# Schematic.net
KiCad netlist of a schematic drawn in Altium Designer
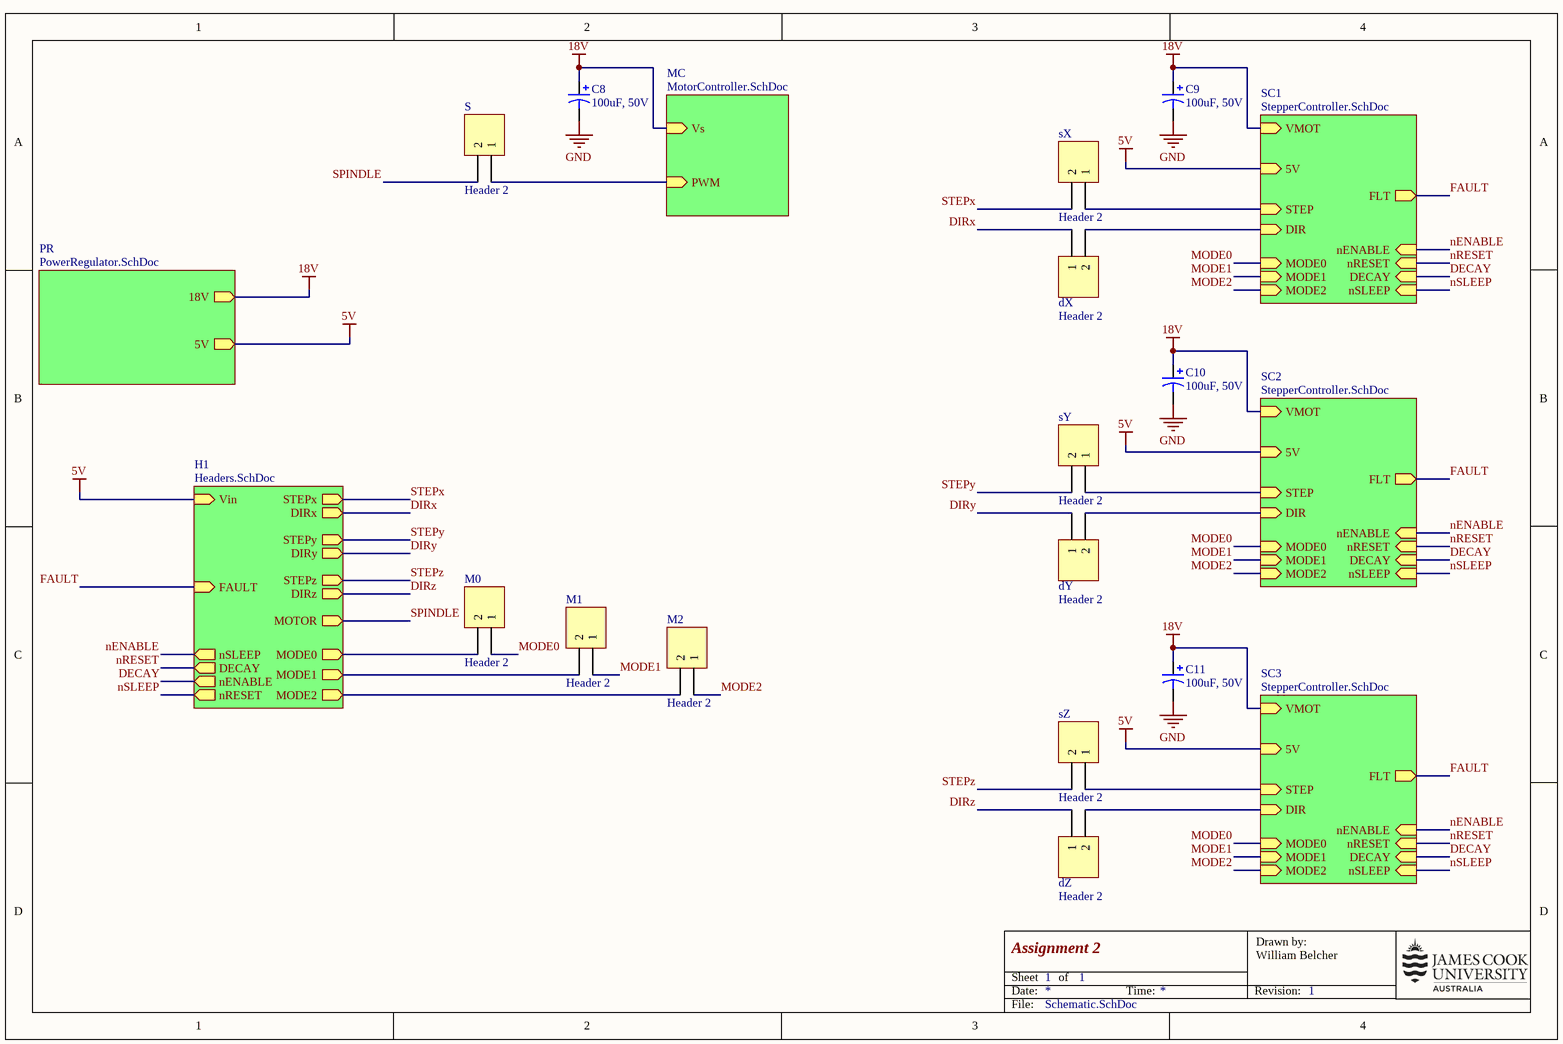
[diagram p0: Schematic.SchDoc]

(export (version "E")
  (design (tool "Eeschema 10.0.6"))
  (components
    (comp (ref "C8")
      (value "100uF, 50V")
      (footprint "Capacitor radial 8mm")
      (description "Electrolytic Capacitor, 100 µF, 50 V, ± 20%, Radial Leaded, 8 mm")
      (libsource (lib "JCULibrary_AS2") (part "Cap 100uF, 50V, THT radial"))
    )
    (comp (ref "C9")
      (value "100uF, 50V")
      (footprint "Capacitor radial 8mm")
      (description "Electrolytic Capacitor, 100 µF, 50 V, ± 20%, Radial Leaded, 8 mm")
      (libsource (lib "JCULibrary_AS2") (part "Cap 100uF, 50V, THT radial"))
    )
    (comp (ref "C10")
      (value "100uF, 50V")
      (footprint "Capacitor radial 8mm")
      (description "Electrolytic Capacitor, 100 µF, 50 V, ± 20%, Radial Leaded, 8 mm")
      (libsource (lib "JCULibrary_AS2") (part "Cap 100uF, 50V, THT radial"))
    )
    (comp (ref "C11")
      (value "100uF, 50V")
      (footprint "Capacitor radial 8mm")
      (description "Electrolytic Capacitor, 100 µF, 50 V, ± 20%, Radial Leaded, 8 mm")
      (libsource (lib "JCULibrary_AS2") (part "Cap 100uF, 50V, THT radial"))
    )
    (comp (ref "dX")
      (value "Header 2")
      (footprint "HDR1X2")
      (description "Header, 2-Pin")
      (fields (field (name "PUBLISHER") "Altium Limited"))
      (libsource (lib "") (part "Header 2_1"))
    )
    (comp (ref "dY")
      (value "Header 2")
      (footprint "HDR1X2")
      (description "Header, 2-Pin")
      (fields (field (name "PUBLISHER") "Altium Limited"))
      (libsource (lib "") (part "Header 2_1"))
    )
    (comp (ref "dZ")
      (value "Header 2")
      (footprint "HDR1X2")
      (description "Header, 2-Pin")
      (fields (field (name "PUBLISHER") "Altium Limited"))
      (libsource (lib "") (part "Header 2_1"))
    )
    (comp (ref "M0")
      (value "Header 2")
      (footprint "HDR1X2")
      (description "Header, 2-Pin")
      (fields (field (name "PUBLISHER") "Altium Limited"))
      (libsource (lib "Miscellaneous Connectors") (part "Header 2"))
    )
    (comp (ref "M1")
      (value "Header 2")
      (footprint "HDR1X2")
      (description "Header, 2-Pin")
      (fields (field (name "PUBLISHER") "Altium Limited"))
      (libsource (lib "Miscellaneous Connectors") (part "Header 2"))
    )
    (comp (ref "M2")
      (value "Header 2")
      (footprint "HDR1X2")
      (description "Header, 2-Pin")
      (fields (field (name "PUBLISHER") "Altium Limited"))
      (libsource (lib "Miscellaneous Connectors") (part "Header 2"))
    )
    (comp (ref "S")
      (value "Header 2")
      (footprint "HDR1X2")
      (description "Header, 2-Pin")
      (fields (field (name "PUBLISHER") "Altium Limited"))
      (libsource (lib "Miscellaneous Connectors") (part "Header 2"))
    )
    (comp (ref "sX")
      (value "Header 2")
      (footprint "HDR1X2")
      (description "Header, 2-Pin")
      (fields (field (name "PUBLISHER") "Altium Limited"))
      (libsource (lib "Miscellaneous Connectors") (part "Header 2"))
    )
    (comp (ref "sY")
      (value "Header 2")
      (footprint "HDR1X2")
      (description "Header, 2-Pin")
      (fields (field (name "PUBLISHER") "Altium Limited"))
      (libsource (lib "Miscellaneous Connectors") (part "Header 2"))
    )
    (comp (ref "sZ")
      (value "Header 2")
      (footprint "HDR1X2")
      (description "Header, 2-Pin")
      (fields (field (name "PUBLISHER") "Altium Limited"))
      (libsource (lib "Miscellaneous Connectors") (part "Header 2"))
    )
  )
  (nets
    (net (code "2") (name "/DIR") (class "Default")
      (node (ref "dY") (pin "2") (pinfunction "2_2") (pintype "passive"))
    )
    (net (code "3") (name "/DIR_1") (class "Default")
      (node (ref "dZ") (pin "2") (pinfunction "2_2") (pintype "passive"))
    )
    (net (code "4") (name "/DIR_2") (class "Default")
      (node (ref "dX") (pin "2") (pinfunction "2_2") (pintype "passive"))
    )
    (net (code "5") (name "/DIRx") (class "Default")
      (node (ref "dX") (pin "1") (pinfunction "1_1") (pintype "passive"))
    )
    (net (code "6") (name "/DIRy") (class "Default")
      (node (ref "dY") (pin "1") (pinfunction "1_1") (pintype "passive"))
    )
    (net (code "7") (name "/DIRz") (class "Default")
      (node (ref "dZ") (pin "1") (pinfunction "1_1") (pintype "passive"))
    )
    (net (code "9") (name "/MODE0") (class "Default")
      (node (ref "M0") (pin "1") (pinfunction "1_1") (pintype "passive"))
    )
    (net (code "10") (name "/MODE0_1") (class "Default")
      (node (ref "M0") (pin "2") (pinfunction "2_2") (pintype "passive"))
    )
    (net (code "11") (name "/MODE1") (class "Default")
      (node (ref "M1") (pin "1") (pinfunction "1_1") (pintype "passive"))
    )
    (net (code "12") (name "/MODE1_1") (class "Default")
      (node (ref "M1") (pin "2") (pinfunction "2_2") (pintype "passive"))
    )
    (net (code "13") (name "/MODE2") (class "Default")
      (node (ref "M2") (pin "1") (pinfunction "1_1") (pintype "passive"))
    )
    (net (code "14") (name "/MODE2_1") (class "Default")
      (node (ref "M2") (pin "2") (pinfunction "2_2") (pintype "passive"))
    )
    (net (code "15") (name "/PWM") (class "Default")
      (node (ref "S") (pin "1") (pinfunction "1_1") (pintype "passive"))
    )
    (net (code "16") (name "/SPINDLE") (class "Default")
      (node (ref "S") (pin "2") (pinfunction "2_2") (pintype "passive"))
    )
    (net (code "17") (name "/STEP") (class "Default")
      (node (ref "sY") (pin "1") (pinfunction "1_1") (pintype "passive"))
    )
    (net (code "18") (name "/STEP_1") (class "Default")
      (node (ref "sZ") (pin "1") (pinfunction "1_1") (pintype "passive"))
    )
    (net (code "19") (name "/STEP_2") (class "Default")
      (node (ref "sX") (pin "1") (pinfunction "1_1") (pintype "passive"))
    )
    (net (code "20") (name "/STEPx") (class "Default")
      (node (ref "sX") (pin "2") (pinfunction "2_2") (pintype "passive"))
    )
    (net (code "21") (name "/STEPy") (class "Default")
      (node (ref "sY") (pin "2") (pinfunction "2_2") (pintype "passive"))
    )
    (net (code "22") (name "/STEPz") (class "Default")
      (node (ref "sZ") (pin "2") (pinfunction "2_2") (pintype "passive"))
    )
    (net (code "27") (name "18V") (class "Default")
      (node (ref "C10") (pin "1") (pinfunction "1_1") (pintype "passive"))
      (node (ref "C11") (pin "1") (pinfunction "1_1") (pintype "passive"))
      (node (ref "C8") (pin "1") (pinfunction "1_1") (pintype "passive"))
      (node (ref "C9") (pin "1") (pinfunction "1_1") (pintype "passive"))
    )
    (net (code "28") (name "GND") (class "Default")
      (node (ref "C10") (pin "2") (pinfunction "2_2") (pintype "passive"))
      (node (ref "C11") (pin "2") (pinfunction "2_2") (pintype "passive"))
      (node (ref "C8") (pin "2") (pinfunction "2_2") (pintype "passive"))
      (node (ref "C9") (pin "2") (pinfunction "2_2") (pintype "passive"))
    )
  )
)
